# Combine-CPU-POWER-RELAY-smd.net
KiCad netlist of a schematic drawn in EAGLE
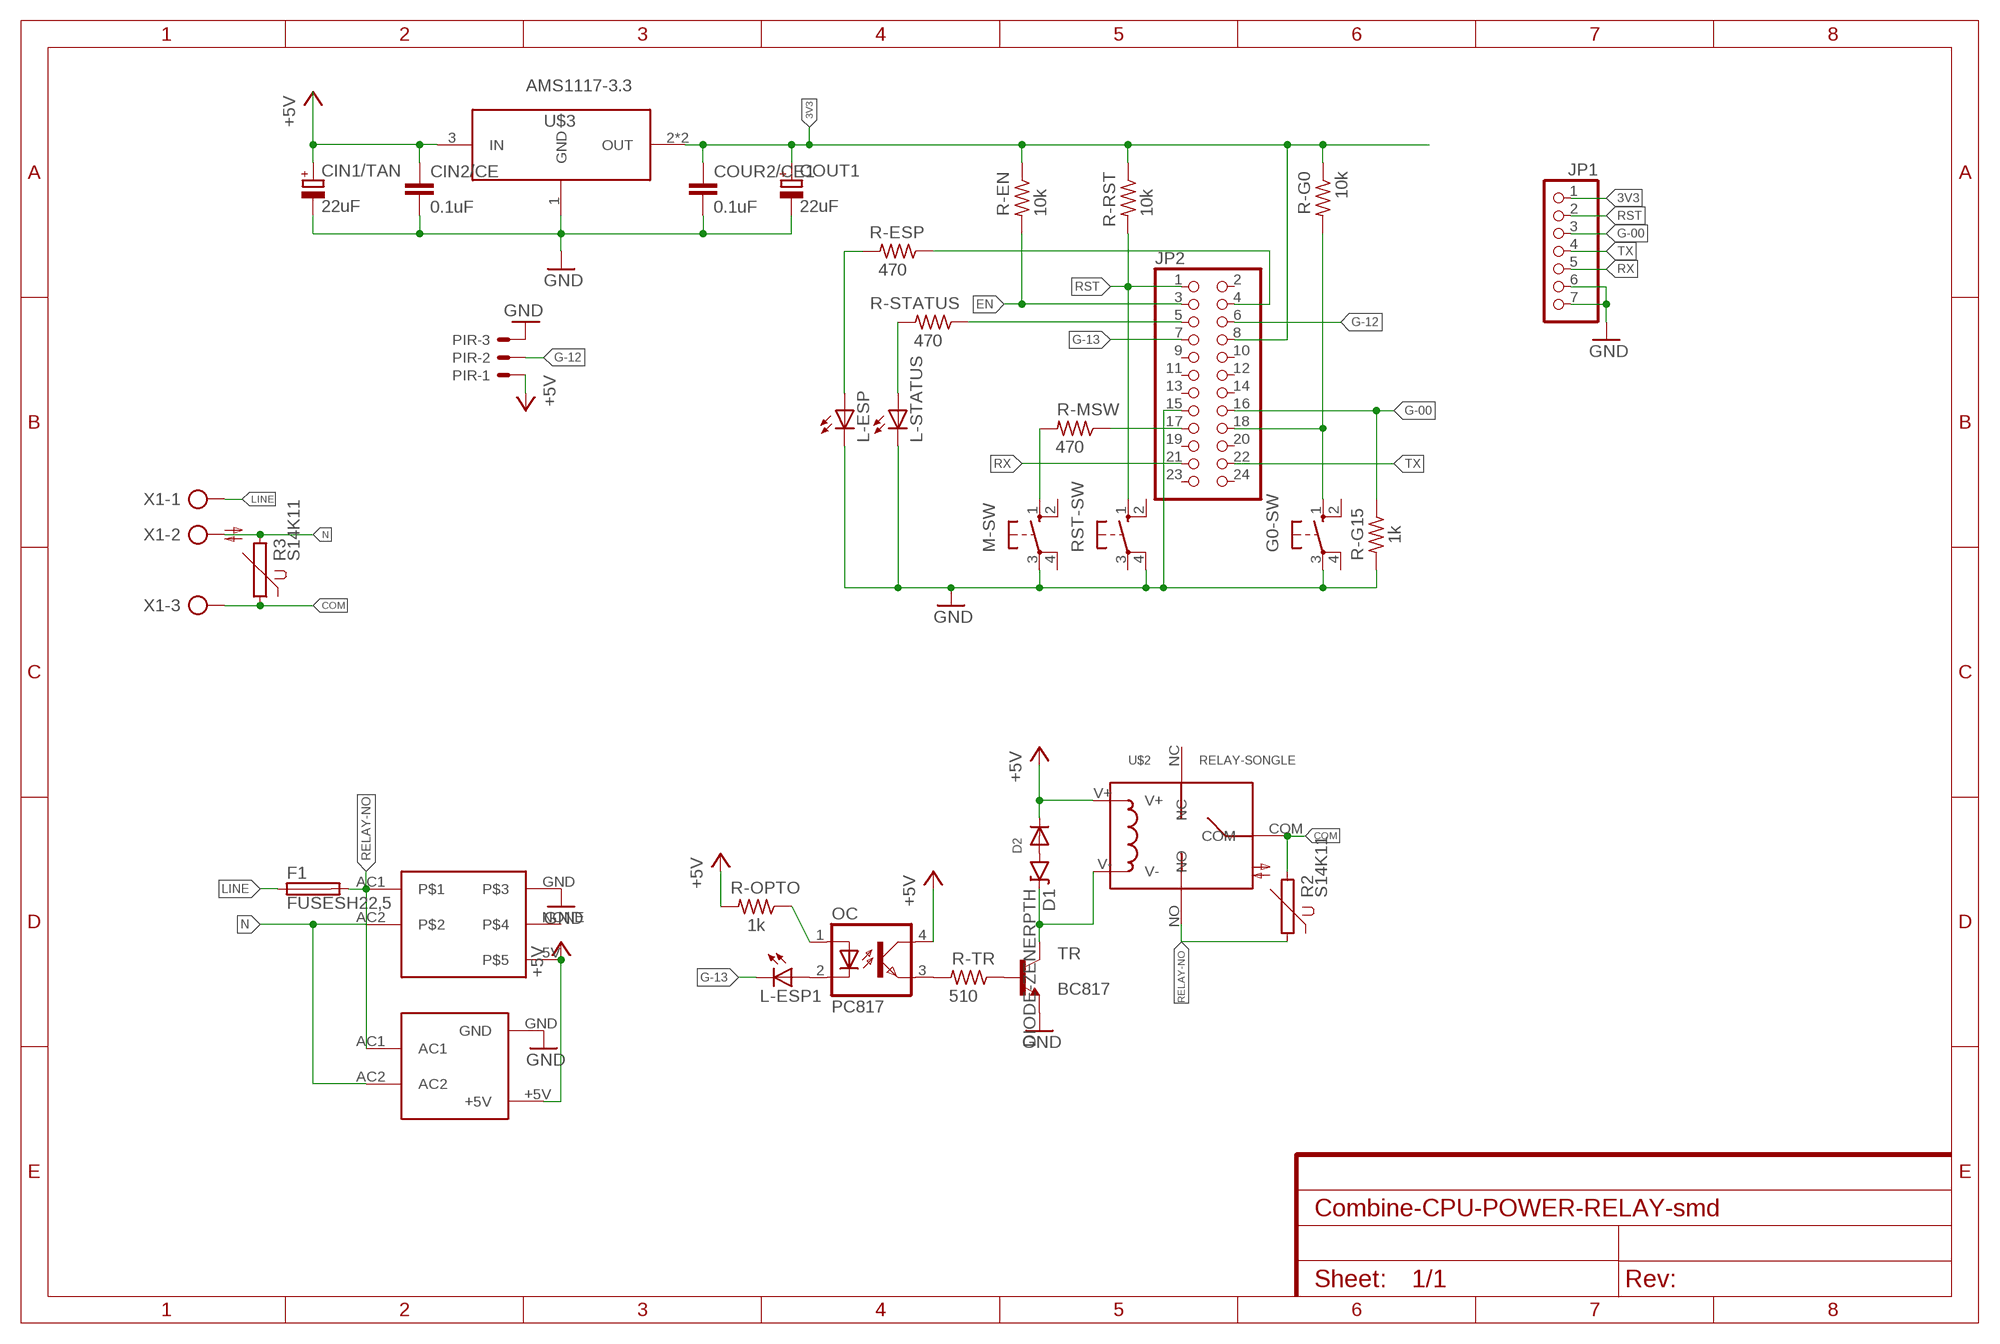
[diagram p0: schematic, sheet 1]

(export (version "E")
  (design (tool "Eeschema 10.0.6"))
  (components
    (comp (ref "CIN1/TAN")
      (value "22uF")
      (footprint "eagle-import:B_3528-21R")
      (libsource (lib "eagle-import") (part "CPOL-EUB/3528-21R"))
    )
    (comp (ref "CIN2/CE")
      (value "0.1uF")
      (footprint "eagle-import:C0805")
      (libsource (lib "eagle-import") (part "C-EUC0805"))
    )
    (comp (ref "COUR2/CE1")
      (value "0.1uF")
      (footprint "eagle-import:C0805")
      (libsource (lib "eagle-import") (part "C-EUC0805"))
    )
    (comp (ref "COUT1")
      (value "22uF")
      (footprint "eagle-import:B_3528-21R")
      (libsource (lib "eagle-import") (part "CPOL-EUB/3528-21R"))
    )
    (comp (ref "D1")
      (value "DIODE-ZENERPTH")
      (footprint "eagle-import:DIODE-ZENER")
      (libsource (lib "eagle-import") (part "DIODE-ZENERPTH"))
    )
    (comp (ref "D2")
      (value "DIODESMA")
      (footprint "eagle-import:SMADIODE")
      (libsource (lib "eagle-import") (part "DIODESMA"))
    )
    (comp (ref "F1")
      (value "FUSESH22,5")
      (footprint "eagle-import:SH22,5")
      (libsource (lib "eagle-import") (part "FUSESH22,5"))
    )
    (comp (ref "G0-SW")
      (value "10-XX")
      (footprint "eagle-import:B3F-10XX")
      (fields (field (name "MPN") "B3F-1000"))
      (libsource (lib "eagle-import") (part "10-XX"))
    )
    (comp (ref "JP1")
      (value "PINHD-1X7")
      (footprint "eagle-import:1X07")
      (libsource (lib "eagle-import") (part "PINHD-1X7"))
    )
    (comp (ref "JP2")
      (value "PINHD-2X12")
      (footprint "eagle-import:2X12")
      (libsource (lib "eagle-import") (part "PINHD-2X12"))
    )
    (comp (ref "L-ESP")
      (value "LED3MM")
      (footprint "eagle-import:LED3MM")
      (libsource (lib "eagle-import") (part "LED3MM"))
    )
    (comp (ref "L-ESP1")
      (value "LED3MM")
      (footprint "eagle-import:LED3MM")
      (libsource (lib "eagle-import") (part "LED3MM"))
    )
    (comp (ref "L-STATUS")
      (value "LED3MM")
      (footprint "eagle-import:LED3MM")
      (libsource (lib "eagle-import") (part "LED3MM"))
    )
    (comp (ref "M-SW")
      (value "10-XX")
      (footprint "eagle-import:B3F-10XX")
      (fields (field (name "MPN") "B3F-1000"))
      (libsource (lib "eagle-import") (part "10-XX"))
    )
    (comp (ref "OC")
      (value "PC817")
      (footprint "eagle-import:DIL04")
      (fields (field (name "MPN") "PC817X4J000F"))
      (libsource (lib "eagle-import") (part "PC817"))
    )
    (comp (ref "PIR")
      (value "53048-03")
      (footprint "eagle-import:53048-03")
      (fields (field (name "MF") "WALDOM/MOLEX") (field (name "MPN") "53048-0310"))
      (libsource (lib "eagle-import") (part "53?-03048"))
    )
    (comp (ref "R-EN")
      (value "10k")
      (footprint "eagle-import:M0805")
      (libsource (lib "eagle-import") (part "R-US_M0805"))
    )
    (comp (ref "R-ESP")
      (value "470")
      (footprint "eagle-import:M0805")
      (libsource (lib "eagle-import") (part "R-US_M0805"))
    )
    (comp (ref "R-G0")
      (value "10k")
      (footprint "eagle-import:M0805")
      (libsource (lib "eagle-import") (part "R-US_M0805"))
    )
    (comp (ref "R-G15")
      (value "1k")
      (footprint "eagle-import:M0805")
      (libsource (lib "eagle-import") (part "R-US_M0805"))
    )
    (comp (ref "R-MSW")
      (value "470")
      (footprint "eagle-import:M0805")
      (libsource (lib "eagle-import") (part "R-US_M0805"))
    )
    (comp (ref "R-OPTO")
      (value "1k")
      (footprint "eagle-import:M0805")
      (libsource (lib "eagle-import") (part "R-US_M0805"))
    )
    (comp (ref "R-RST")
      (value "10k")
      (footprint "eagle-import:M0805")
      (libsource (lib "eagle-import") (part "R-US_M0805"))
    )
    (comp (ref "R-STATUS")
      (value "470")
      (footprint "eagle-import:M0805")
      (libsource (lib "eagle-import") (part "R-US_M0805"))
    )
    (comp (ref "R-TR")
      (value "510")
      (footprint "eagle-import:M0805")
      (libsource (lib "eagle-import") (part "R-US_M0805"))
    )
    (comp (ref "R2")
      (value "S14K11")
      (footprint "eagle-import:S14K11")
      (libsource (lib "eagle-import") (part "S14K11"))
    )
    (comp (ref "R3")
      (value "S14K11")
      (footprint "eagle-import:S14K11")
      (libsource (lib "eagle-import") (part "S14K11"))
    )
    (comp (ref "RST-SW")
      (value "10-XX")
      (footprint "eagle-import:B3F-10XX")
      (fields (field (name "MPN") "B3F-1000"))
      (libsource (lib "eagle-import") (part "10-XX"))
    )
    (comp (ref "TR")
      (value "BC817")
      (footprint "eagle-import:SOT23-BEC")
      (libsource (lib "eagle-import") (part "BC817SMD-16"))
    )
    (comp (ref "U$1")
      (value "HLK-PM01")
      (footprint "eagle-import:HLK-PM01")
      (libsource (lib "eagle-import") (part "HLK-PM01"))
    )
    (comp (ref "U$2")
      (value "RELAY-SONGLE")
      (footprint "eagle-import:RELAY-SONGLE")
      (libsource (lib "eagle-import") (part "RELAY-SONGLE"))
    )
    (comp (ref "U$3")
      (value "AMS1117-3.3")
      (footprint "eagle-import:SOT-223")
      (libsource (lib "eagle-import") (part "AMS1117-3.3"))
    )
    (comp (ref "U$4")
      (value "POWERSUPPLY-5V-700MA")
      (footprint "eagle-import:POWERSUPPLY-5V-700MA")
      (libsource (lib "eagle-import") (part "POWERSUPPLY-5V-700MA"))
    )
    (comp (ref "X1")
      (value "AK300/3")
      (footprint "eagle-import:AK300_3")
      (libsource (lib "eagle-import") (part "AK300/3"))
    )
  )
  (nets
    (net (code "1") (name "+5V") (class "Default")
      (node (ref "CIN1/TAN") (pin "+") (pinfunction "+_+") (pintype "passive"))
      (node (ref "CIN2/CE") (pin "1") (pinfunction "1_1") (pintype "passive"))
      (node (ref "D2") (pin "C") (pinfunction "C_C") (pintype "passive"))
      (node (ref "OC") (pin "4") (pinfunction "COL_4") (pintype "passive"))
      (node (ref "PIR") (pin "1") (pinfunction "S_1") (pintype "passive"))
      (node (ref "R-OPTO") (pin "2") (pinfunction "2_2") (pintype "passive"))
      (node (ref "U$1") (pin "+5V") (pinfunction "+5V_+5V") (pintype "bidirectional"))
      (node (ref "U$2") (pin "V+") (pinfunction "V+_V+") (pintype "bidirectional"))
      (node (ref "U$3") (pin "3") (pinfunction "IN_3") (pintype "input"))
      (node (ref "U$4") (pin "5V") (pinfunction "P$5_5V") (pintype "bidirectional"))
    )
    (net (code "2") (name "3V3") (class "Default")
      (node (ref "COUR2/CE1") (pin "1") (pinfunction "1_1") (pintype "passive"))
      (node (ref "COUT1") (pin "+") (pinfunction "+_+") (pintype "passive"))
      (node (ref "JP1") (pin "1") (pinfunction "1_1") (pintype "passive"))
      (node (ref "JP2") (pin "8") (pinfunction "8_8") (pintype "passive"))
      (node (ref "R-EN") (pin "1") (pinfunction "1_1") (pintype "passive"))
      (node (ref "R-G0") (pin "1") (pinfunction "1_1") (pintype "passive"))
      (node (ref "R-RST") (pin "1") (pinfunction "1_1") (pintype "passive"))
      (node (ref "U$3") (pin "2") (pinfunction "OUT_2") (pintype "output"))
      (node (ref "U$3") (pin "4") (pinfunction "OUT_4") (pintype "output"))
    )
    (net (code "3") (name "COM") (class "Default")
      (node (ref "R2") (pin "2") (pinfunction "2_2") (pintype "passive"))
      (node (ref "R3") (pin "1") (pinfunction "1_1") (pintype "passive"))
      (node (ref "U$2") (pin "COM") (pinfunction "COM_COM") (pintype "bidirectional"))
      (node (ref "X1") (pin "3") (pinfunction "KL_3") (pintype "passive"))
    )
    (net (code "4") (name "EN") (class "Default")
      (node (ref "JP2") (pin "3") (pinfunction "3_3") (pintype "passive"))
      (node (ref "R-EN") (pin "2") (pinfunction "2_2") (pintype "passive"))
    )
    (net (code "5") (name "G-00") (class "Default")
      (node (ref "JP1") (pin "3") (pinfunction "3_3") (pintype "passive"))
      (node (ref "JP2") (pin "16") (pinfunction "16_16") (pintype "passive"))
      (node (ref "R-G15") (pin "1") (pinfunction "1_1") (pintype "passive"))
    )
    (net (code "6") (name "G-12") (class "Default")
      (node (ref "JP2") (pin "6") (pinfunction "6_6") (pintype "passive"))
      (node (ref "PIR") (pin "2") (pinfunction "S_2") (pintype "passive"))
    )
    (net (code "7") (name "G-13") (class "Default")
      (node (ref "JP2") (pin "7") (pinfunction "7_7") (pintype "passive"))
      (node (ref "L-ESP1") (pin "K") (pinfunction "C_K") (pintype "passive"))
    )
    (net (code "8") (name "GND") (class "Default")
      (node (ref "CIN1/TAN") (pin "-") (pinfunction "-_-") (pintype "passive"))
      (node (ref "CIN2/CE") (pin "2") (pinfunction "2_2") (pintype "passive"))
      (node (ref "COUR2/CE1") (pin "2") (pinfunction "2_2") (pintype "passive"))
      (node (ref "COUT1") (pin "-") (pinfunction "-_-") (pintype "passive"))
      (node (ref "G0-SW") (pin "3") (pinfunction "P_3") (pintype "passive"))
      (node (ref "JP1") (pin "6") (pinfunction "6_6") (pintype "passive"))
      (node (ref "JP1") (pin "7") (pinfunction "7_7") (pintype "passive"))
      (node (ref "JP2") (pin "15") (pinfunction "15_15") (pintype "passive"))
      (node (ref "L-ESP") (pin "K") (pinfunction "C_K") (pintype "passive"))
      (node (ref "L-STATUS") (pin "K") (pinfunction "C_K") (pintype "passive"))
      (node (ref "M-SW") (pin "3") (pinfunction "P_3") (pintype "passive"))
      (node (ref "PIR") (pin "3") (pinfunction "S_3") (pintype "passive"))
      (node (ref "R-G15") (pin "2") (pinfunction "2_2") (pintype "passive"))
      (node (ref "RST-SW") (pin "4") (pinfunction "P1_4") (pintype "passive"))
      (node (ref "TR") (pin "E") (pinfunction "E_E") (pintype "passive"))
      (node (ref "U$1") (pin "GND") (pinfunction "GND_GND") (pintype "bidirectional"))
      (node (ref "U$3") (pin "1") (pinfunction "GND_1") (pintype "passive"))
      (node (ref "U$4") (pin "GND") (pinfunction "P$3_GND") (pintype "bidirectional"))
    )
    (net (code "9") (name "LINE") (class "Default")
      (node (ref "F1") (pin "1") (pinfunction "1_1") (pintype "passive"))
      (node (ref "X1") (pin "1") (pinfunction "KL_1") (pintype "passive"))
    )
    (net (code "10") (name "N") (class "Default")
      (node (ref "R3") (pin "2") (pinfunction "2_2") (pintype "passive"))
      (node (ref "U$1") (pin "AC2") (pinfunction "AC2_AC2") (pintype "bidirectional"))
      (node (ref "U$4") (pin "AC2") (pinfunction "P$2_AC2") (pintype "bidirectional"))
      (node (ref "X1") (pin "2") (pinfunction "KL_2") (pintype "passive"))
    )
    (net (code "11") (name "Net-(D1-A)") (class "Default")
      (node (ref "D1") (pin "P$2") (pinfunction "A_P$2") (pintype "passive"))
      (node (ref "D2") (pin "A") (pinfunction "A_A") (pintype "passive"))
    )
    (net (code "12") (name "Net-(D1-C)") (class "Default")
      (node (ref "D1") (pin "P$1") (pinfunction "C_P$1") (pintype "passive"))
      (node (ref "TR") (pin "C") (pinfunction "C_C") (pintype "passive"))
      (node (ref "U$2") (pin "V-") (pinfunction "V-_V-") (pintype "bidirectional"))
    )
    (net (code "13") (name "Net-(G0-SW-S)") (class "Default")
      (node (ref "G0-SW") (pin "1") (pinfunction "S_1") (pintype "passive"))
      (node (ref "JP2") (pin "18") (pinfunction "18_18") (pintype "passive"))
      (node (ref "R-G0") (pin "2") (pinfunction "2_2") (pintype "passive"))
    )
    (net (code "14") (name "Net-(JP2-Pad4)") (class "Default")
      (node (ref "JP2") (pin "4") (pinfunction "4_4") (pintype "passive"))
      (node (ref "R-ESP") (pin "1") (pinfunction "1_1") (pintype "passive"))
    )
    (net (code "15") (name "Net-(JP2-Pad5)") (class "Default")
      (node (ref "JP2") (pin "5") (pinfunction "5_5") (pintype "passive"))
      (node (ref "R-STATUS") (pin "1") (pinfunction "1_1") (pintype "passive"))
    )
    (net (code "16") (name "Net-(JP2-Pad17)") (class "Default")
      (node (ref "JP2") (pin "17") (pinfunction "17_17") (pintype "passive"))
      (node (ref "R-MSW") (pin "1") (pinfunction "1_1") (pintype "passive"))
    )
    (net (code "17") (name "Net-(L-ESP-PadA)") (class "Default")
      (node (ref "L-ESP") (pin "A") (pinfunction "A_A") (pintype "passive"))
      (node (ref "R-ESP") (pin "2") (pinfunction "2_2") (pintype "passive"))
    )
    (net (code "18") (name "Net-(L-STATUS-PadA)") (class "Default")
      (node (ref "L-STATUS") (pin "A") (pinfunction "A_A") (pintype "passive"))
      (node (ref "R-STATUS") (pin "2") (pinfunction "2_2") (pintype "passive"))
    )
    (net (code "19") (name "Net-(M-SW-S)") (class "Default")
      (node (ref "M-SW") (pin "1") (pinfunction "S_1") (pintype "passive"))
      (node (ref "R-MSW") (pin "2") (pinfunction "2_2") (pintype "passive"))
    )
    (net (code "20") (name "Net-(OC-A)") (class "Default")
      (node (ref "OC") (pin "1") (pinfunction "A_1") (pintype "passive"))
      (node (ref "R-OPTO") (pin "1") (pinfunction "1_1") (pintype "passive"))
    )
    (net (code "21") (name "Net-(OC-C)") (class "Default")
      (node (ref "L-ESP1") (pin "A") (pinfunction "A_A") (pintype "passive"))
      (node (ref "OC") (pin "2") (pinfunction "C_2") (pintype "passive"))
    )
    (net (code "22") (name "Net-(OC-EMIT)") (class "Default")
      (node (ref "OC") (pin "3") (pinfunction "EMIT_3") (pintype "passive"))
      (node (ref "R-TR") (pin "2") (pinfunction "2_2") (pintype "passive"))
    )
    (net (code "23") (name "Net-(R-TR-Pad1)") (class "Default")
      (node (ref "R-TR") (pin "1") (pinfunction "1_1") (pintype "passive"))
      (node (ref "TR") (pin "B") (pinfunction "B_B") (pintype "passive"))
    )
    (net (code "24") (name "RELAY-NO") (class "Default")
      (node (ref "F1") (pin "2") (pinfunction "2_2") (pintype "passive"))
      (node (ref "R2") (pin "1") (pinfunction "1_1") (pintype "passive"))
      (node (ref "U$1") (pin "AC1") (pinfunction "AC1_AC1") (pintype "bidirectional"))
      (node (ref "U$2") (pin "NO") (pinfunction "NO_NO") (pintype "bidirectional"))
      (node (ref "U$4") (pin "AC1") (pinfunction "P$1_AC1") (pintype "bidirectional"))
    )
    (net (code "25") (name "RST") (class "Default")
      (node (ref "JP1") (pin "2") (pinfunction "2_2") (pintype "passive"))
      (node (ref "JP2") (pin "1") (pinfunction "1_1") (pintype "passive"))
      (node (ref "R-RST") (pin "2") (pinfunction "2_2") (pintype "passive"))
      (node (ref "RST-SW") (pin "1") (pinfunction "S_1") (pintype "passive"))
    )
    (net (code "26") (name "RX") (class "Default")
      (node (ref "JP1") (pin "5") (pinfunction "5_5") (pintype "passive"))
      (node (ref "JP2") (pin "21") (pinfunction "21_21") (pintype "passive"))
    )
    (net (code "27") (name "TX") (class "Default")
      (node (ref "JP1") (pin "4") (pinfunction "4_4") (pintype "passive"))
      (node (ref "JP2") (pin "22") (pinfunction "22_22") (pintype "passive"))
    )
    (net (code "28") (name "unconnected-(G0-SW-P1-Pad4)") (class "Default")
      (node (ref "G0-SW") (pin "4") (pinfunction "P1_4") (pintype "passive"))
    )
    (net (code "29") (name "unconnected-(G0-SW-S1-Pad2)") (class "Default")
      (node (ref "G0-SW") (pin "2") (pinfunction "S1_2") (pintype "passive"))
    )
    (net (code "30") (name "unconnected-(JP2-Pad2)") (class "Default")
      (node (ref "JP2") (pin "2") (pinfunction "2_2") (pintype "passive"))
    )
    (net (code "31") (name "unconnected-(JP2-Pad9)") (class "Default")
      (node (ref "JP2") (pin "9") (pinfunction "9_9") (pintype "passive"))
    )
    (net (code "32") (name "unconnected-(JP2-Pad10)") (class "Default")
      (node (ref "JP2") (pin "10") (pinfunction "10_10") (pintype "passive"))
    )
    (net (code "33") (name "unconnected-(JP2-Pad11)") (class "Default")
      (node (ref "JP2") (pin "11") (pinfunction "11_11") (pintype "passive"))
    )
    (net (code "34") (name "unconnected-(JP2-Pad12)") (class "Default")
      (node (ref "JP2") (pin "12") (pinfunction "12_12") (pintype "passive"))
    )
    (net (code "35") (name "unconnected-(JP2-Pad13)") (class "Default")
      (node (ref "JP2") (pin "13") (pinfunction "13_13") (pintype "passive"))
    )
    (net (code "36") (name "unconnected-(JP2-Pad14)") (class "Default")
      (node (ref "JP2") (pin "14") (pinfunction "14_14") (pintype "passive"))
    )
    (net (code "37") (name "unconnected-(JP2-Pad19)") (class "Default")
      (node (ref "JP2") (pin "19") (pinfunction "19_19") (pintype "passive"))
    )
    (net (code "38") (name "unconnected-(JP2-Pad20)") (class "Default")
      (node (ref "JP2") (pin "20") (pinfunction "20_20") (pintype "passive"))
    )
    (net (code "39") (name "unconnected-(JP2-Pad23)") (class "Default")
      (node (ref "JP2") (pin "23") (pinfunction "23_23") (pintype "passive"))
    )
    (net (code "40") (name "unconnected-(JP2-Pad24)") (class "Default")
      (node (ref "JP2") (pin "24") (pinfunction "24_24") (pintype "passive"))
    )
    (net (code "41") (name "unconnected-(M-SW-P1-Pad4)") (class "Default")
      (node (ref "M-SW") (pin "4") (pinfunction "P1_4") (pintype "passive"))
    )
    (net (code "42") (name "unconnected-(M-SW-S1-Pad2)") (class "Default")
      (node (ref "M-SW") (pin "2") (pinfunction "S1_2") (pintype "passive"))
    )
    (net (code "43") (name "unconnected-(RST-SW-P-Pad3)") (class "Default")
      (node (ref "RST-SW") (pin "3") (pinfunction "P_3") (pintype "passive"))
    )
    (net (code "44") (name "unconnected-(RST-SW-S1-Pad2)") (class "Default")
      (node (ref "RST-SW") (pin "2") (pinfunction "S1_2") (pintype "passive"))
    )
    (net (code "45") (name "unconnected-(U$2-PadNC)") (class "Default")
      (node (ref "U$2") (pin "NC") (pinfunction "NC_NC") (pintype "bidirectional"))
    )
    (net (code "46") (name "unconnected-(U$4-P$4-PadNONE)") (class "Default")
      (node (ref "U$4") (pin "NONE") (pinfunction "P$4_NONE") (pintype "bidirectional"))
    )
  )
)
